# Filtres_PWM_Generateur_Bruit.net
KiCad netlist of a schematic drawn in Altium Designer
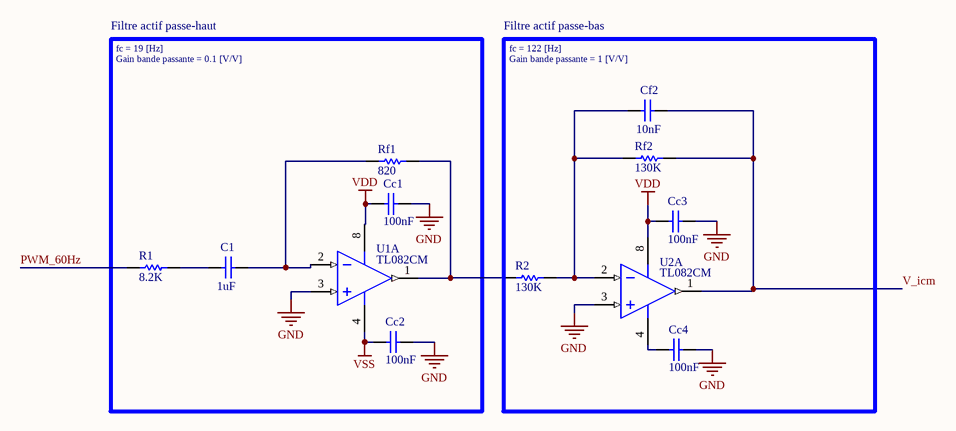
[diagram p0: Filtres_PWM_Generateur_Bruit.SchDoc]

(export (version "E")
  (design (tool "Eeschema 10.0.6"))
  (components
    (comp (ref "C1")
      (value "C333C105M5U5TA")
      (footprint "KEMT-C333C105M5U5TA-2")
      (fields
        (field (name "MANUFACTURER") "Kemet")
        (field (name "CAPACITANCE") "1uF")
        (field (name "TOLERANCE") "20%")
      )
      (libsource (lib "Altium Content Vault") (part "CAP-NP-2"))
    )
    (comp (ref "Cc1")
      (value "100nF")
      (footprint "RAD-0.3")
      (description "Capacitor")
      (fields (field (name "Comment") "Cap") (field (name "PUBLISHER") "Altium Limited"))
      (libsource (lib "Miscellaneous Devices") (part "Cap"))
    )
    (comp (ref "Cc2")
      (value "100nF")
      (footprint "RAD-0.3")
      (description "Capacitor")
      (fields (field (name "Comment") "Cap") (field (name "PUBLISHER") "Altium Limited"))
      (libsource (lib "Miscellaneous Devices") (part "Cap"))
    )
    (comp (ref "Cc3")
      (value "100nF")
      (footprint "RAD-0.3")
      (description "Capacitor")
      (fields (field (name "Comment") "Cap") (field (name "PUBLISHER") "Altium Limited"))
      (libsource (lib "Miscellaneous Devices") (part "Cap"))
    )
    (comp (ref "Cc4")
      (value "100nF")
      (footprint "RAD-0.3")
      (description "Capacitor")
      (fields (field (name "Comment") "Cap") (field (name "PUBLISHER") "Altium Limited"))
      (libsource (lib "Miscellaneous Devices") (part "Cap"))
    )
    (comp (ref "Cf2")
      (value "C333C105M5U5TA")
      (footprint "KEMT-C333C105M5U5TA-2")
      (fields
        (field (name "MANUFACTURER") "Kemet")
        (field (name "CAPACITANCE") "10nF")
        (field (name "TOLERANCE") "20%")
      )
      (libsource (lib "Altium Content Vault") (part "CAP-NP-2"))
    )
    (comp (ref "R1")
      (value "8.2K")
      (footprint "AXIAL-0.3")
      (description "Resistor")
      (fields (field (name "Comment") "Res1") (field (name "PUBLISHER") "Altium Limited"))
      (libsource (lib "Miscellaneous Devices") (part "Res1"))
    )
    (comp (ref "R2")
      (value "130K")
      (footprint "AXIAL-0.3")
      (description "Resistor")
      (fields (field (name "Comment") "Res1") (field (name "PUBLISHER") "Altium Limited"))
      (libsource (lib "Miscellaneous Devices") (part "Res1"))
    )
    (comp (ref "Rf1")
      (value "820")
      (footprint "AXIAL-0.3")
      (description "Resistor")
      (fields (field (name "Comment") "Res1") (field (name "PUBLISHER") "Altium Limited"))
      (libsource (lib "Miscellaneous Devices") (part "Res1"))
    )
    (comp (ref "Rf2")
      (value "130K")
      (footprint "AXIAL-0.3")
      (description "Resistor")
      (fields (field (name "Comment") "Res1") (field (name "PUBLISHER") "Altium Limited"))
      (libsource (lib "Miscellaneous Devices") (part "Res1"))
    )
    (comp (ref "U1")
      (value "TL082CM")
      (footprint "M08A_N")
      (description "Wide Bandwidth Dual JFET Input Operational Amplifier, 8-pin Narrow SOIC")
      (fields
        (field (name "MANUFACTURER") "National Semiconductor")
        (field (name "PUBLISHER") "Altium Limited")
      )
      (libsource (lib "NSC_Amplifier2026") (part "TL082CM"))
    )
    (comp (ref "U2")
      (value "TL082CM")
      (footprint "M08A_N")
      (description "Wide Bandwidth Dual JFET Input Operational Amplifier, 8-pin Narrow SOIC")
      (fields
        (field (name "MANUFACTURER") "National Semiconductor")
        (field (name "PUBLISHER") "Altium Limited")
      )
      (libsource (lib "NSC_Amplifier2026") (part "TL082CM"))
    )
  )
  (nets
    (net (code "1") (name "/PWM_60Hz") (class "Default")
      (node (ref "R1") (pin "1") (pinfunction "1_1") (pintype "passive"))
    )
    (net (code "2") (name "/V_icm") (class "Default")
      (node (ref "Cf2") (pin "2") (pinfunction "2_2") (pintype "passive"))
      (node (ref "Rf2") (pin "2") (pinfunction "2_2") (pintype "passive"))
      (node (ref "U2") (pin "1") (pinfunction "OUTA_1") (pintype "output"))
    )
    (net (code "3") (name "GND") (class "Default")
      (node (ref "Cc1") (pin "2") (pinfunction "2_2") (pintype "passive"))
      (node (ref "Cc2") (pin "2") (pinfunction "2_2") (pintype "passive"))
      (node (ref "Cc3") (pin "2") (pinfunction "2_2") (pintype "passive"))
      (node (ref "Cc4") (pin "2") (pinfunction "2_2") (pintype "passive"))
      (node (ref "U1") (pin "3") (pinfunction "INA+_3") (pintype "input"))
      (node (ref "U2") (pin "3") (pinfunction "INA+_3") (pintype "input"))
    )
    (net (code "4") (name "Net-(C1-Pad1)") (class "Default")
      (node (ref "C1") (pin "1") (pinfunction "1_1") (pintype "passive"))
      (node (ref "R1") (pin "2") (pinfunction "2_2") (pintype "passive"))
    )
    (net (code "5") (name "Net-(U1A-INA-)") (class "Default")
      (node (ref "C1") (pin "2") (pinfunction "2_2") (pintype "passive"))
      (node (ref "Rf1") (pin "1") (pinfunction "1_1") (pintype "passive"))
      (node (ref "U1") (pin "2") (pinfunction "INA-_2") (pintype "input"))
    )
    (net (code "6") (name "Net-(U1A-OUTA)") (class "Default")
      (node (ref "R2") (pin "1") (pinfunction "1_1") (pintype "passive"))
      (node (ref "Rf1") (pin "2") (pinfunction "2_2") (pintype "passive"))
      (node (ref "U1") (pin "1") (pinfunction "OUTA_1") (pintype "output"))
    )
    (net (code "7") (name "Net-(U2A-INA-)") (class "Default")
      (node (ref "Cf2") (pin "1") (pinfunction "1_1") (pintype "passive"))
      (node (ref "R2") (pin "2") (pinfunction "2_2") (pintype "passive"))
      (node (ref "Rf2") (pin "1") (pinfunction "1_1") (pintype "passive"))
      (node (ref "U2") (pin "2") (pinfunction "INA-_2") (pintype "input"))
    )
    (net (code "8") (name "Net-(U2A-V-)") (class "Default")
      (node (ref "Cc4") (pin "1") (pinfunction "1_1") (pintype "passive"))
      (node (ref "U2") (pin "4") (pinfunction "V-_4") (pintype "power_in"))
    )
    (net (code "9") (name "VDD") (class "Default")
      (node (ref "Cc1") (pin "1") (pinfunction "1_1") (pintype "passive"))
      (node (ref "Cc3") (pin "1") (pinfunction "1_1") (pintype "passive"))
      (node (ref "U1") (pin "8") (pinfunction "V+_8") (pintype "power_in"))
      (node (ref "U2") (pin "8") (pinfunction "V+_8") (pintype "power_in"))
    )
    (net (code "10") (name "VSS") (class "Default")
      (node (ref "Cc2") (pin "1") (pinfunction "1_1") (pintype "passive"))
      (node (ref "U1") (pin "4") (pinfunction "V-_4") (pintype "power_in"))
    )
  )
)
